# 7_LCD.net
KiCad netlist of a schematic drawn in Altium Designer
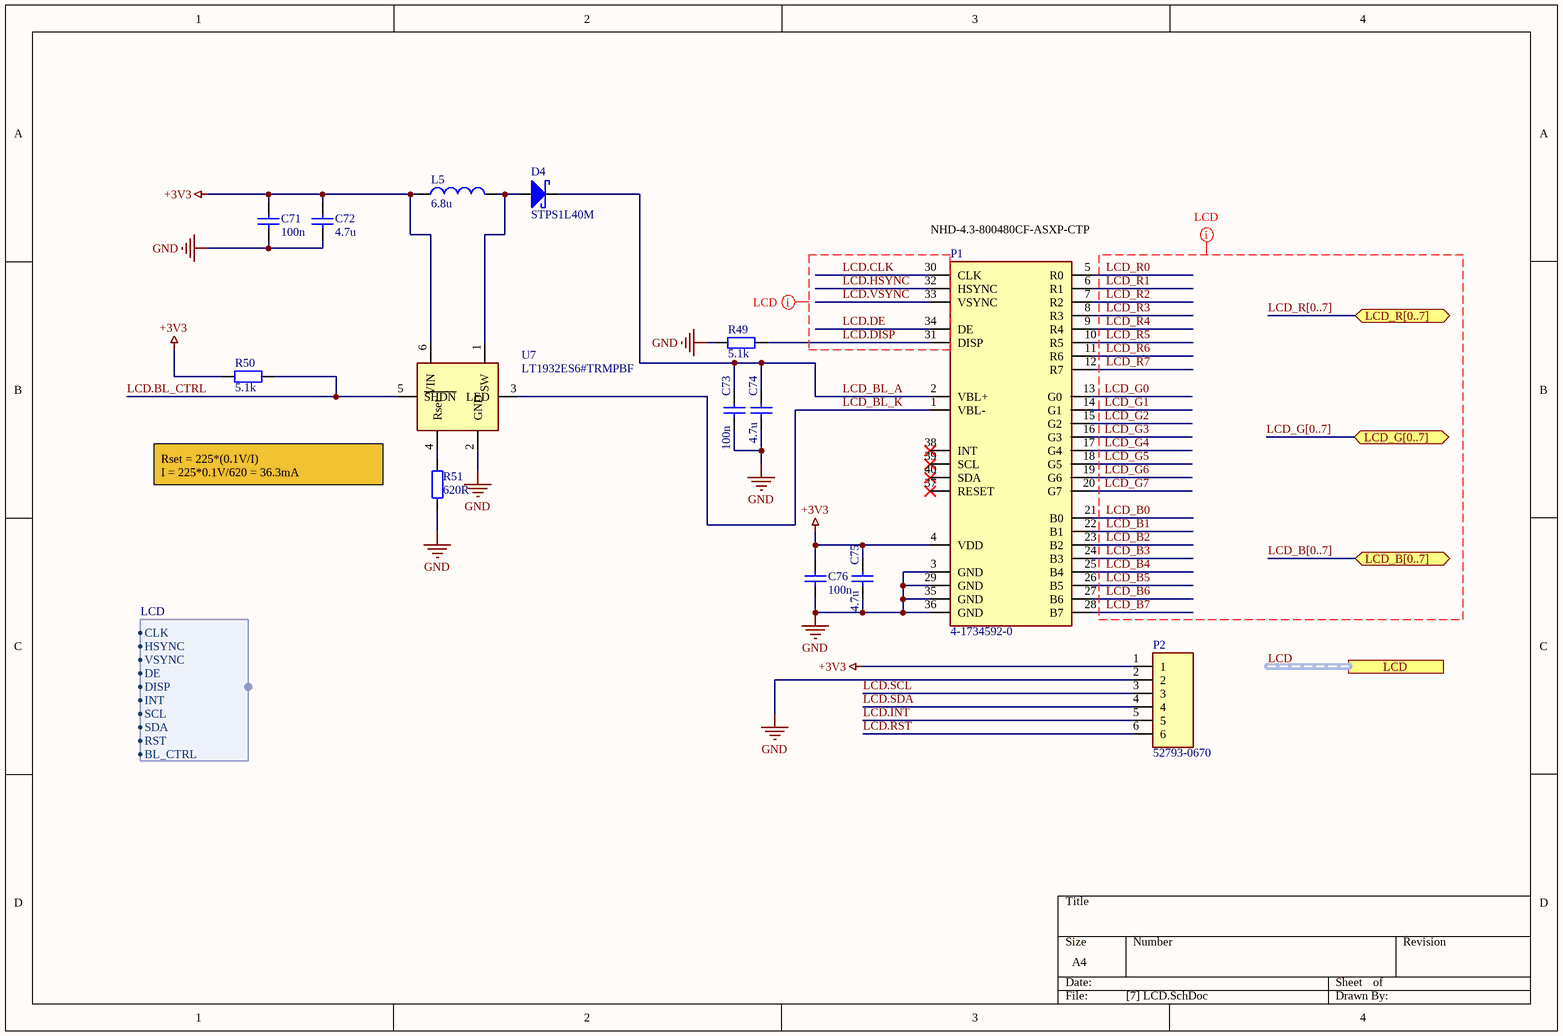
[diagram p0: [7] LCD.SchDoc]

(export (version "E")
  (design (tool "Eeschema 10.0.6"))
  (components
    (comp (ref "C71")
      (value "100n")
      (footprint "STguitar:Capacitor 0603")
      (description "Multilayer Ceramic Capacitors MLCC - SMD/SMT 0603 16VDC 0.1uF 10% X7R")
      (fields
        (field (name "MANUFACTURER PART NUMBER") "EMK107B7104KA-T")
        (field (name "MANUFACTURER") "Taiyo Yuden")
      )
      (libsource (lib "STguitar") (part "Capacitor 100n 10% 0603 EMK107B7104KA-T"))
    )
    (comp (ref "C72")
      (value "4.7u")
      (footprint "STguitar:Capacitor 0603")
      (description "Multilayer Ceramic Capacitors MLCC - SMD/SMT 0603 16VDC 4.7uF 10% X5R")
      (fields
        (field (name "MANUFACTURER PART NUMBER") "EMK107ABJ475KA-T")
        (field (name "MANUFACTURER") "Taiyo Yuden")
      )
      (libsource (lib "STguitar") (part "Capacitor 4.7u 10% 0603 EMK107ABJ475KA-T"))
    )
    (comp (ref "C73")
      (value "100n")
      (footprint "STguitar:Capacitor 0603")
      (description "Multilayer Ceramic Capacitors MLCC - SMD/SMT 0603 16VDC 0.1uF 10% X7R")
      (fields
        (field (name "MANUFACTURER PART NUMBER") "EMK107B7104KA-T")
        (field (name "MANUFACTURER") "Taiyo Yuden")
      )
      (libsource (lib "STguitar") (part "Capacitor 100n 10% 0603 EMK107B7104KA-T"))
    )
    (comp (ref "C74")
      (value "4.7u")
      (footprint "STguitar:Capacitor 0603")
      (description "Multilayer Ceramic Capacitors MLCC - SMD/SMT 0603 16VDC 4.7uF 10% X5R")
      (fields
        (field (name "MANUFACTURER PART NUMBER") "EMK107ABJ475KA-T")
        (field (name "MANUFACTURER") "Taiyo Yuden")
      )
      (libsource (lib "STguitar") (part "Capacitor 4.7u 10% 0603 EMK107ABJ475KA-T"))
    )
    (comp (ref "C75")
      (value "4.7u")
      (footprint "STguitar:Capacitor 0603")
      (description "Multilayer Ceramic Capacitors MLCC - SMD/SMT 0603 16VDC 4.7uF 10% X5R")
      (fields
        (field (name "MANUFACTURER PART NUMBER") "EMK107ABJ475KA-T")
        (field (name "MANUFACTURER") "Taiyo Yuden")
      )
      (libsource (lib "STguitar") (part "Capacitor 4.7u 10% 0603 EMK107ABJ475KA-T"))
    )
    (comp (ref "C76")
      (value "100n")
      (footprint "STguitar:Capacitor 0603")
      (description "Multilayer Ceramic Capacitors MLCC - SMD/SMT 0603 16VDC 0.1uF 10% X7R")
      (fields
        (field (name "MANUFACTURER PART NUMBER") "EMK107B7104KA-T")
        (field (name "MANUFACTURER") "Taiyo Yuden")
      )
      (libsource (lib "STguitar") (part "Capacitor 100n 10% 0603 EMK107B7104KA-T"))
    )
    (comp (ref "D4")
      (value "STPS1L40M")
      (footprint "STguitar:DO216-AA")
      (description "Schottky Diodes & Rectifiers 1.0 Amp 40 Volt")
      (fields (field (name "MANUFACTURER") "ON Semiconductor / Fairchild"))
      (libsource (lib "STguitar") (part "Diode Schottky Diodes & Rectifiers 1.0 Amp 40 Volt STPS1L40M"))
    )
    (comp (ref "L5")
      (value "6.8u")
      (footprint "STguitar:Inductor ASPI")
      (description "Fixed Inductors FIXED IND 6.8UH 900MA 295 MOHM")
      (fields
        (field (name "MANUFACTURER PART NUMBER") "ASPI-2515-6R8M-T2")
        (field (name "MANUFACTURER") "ABRACON")
      )
      (libsource (lib "STguitar") (part "Inductor FIXED IND 6.8UH 900MA 295 MOHM ASPI-2515-6R8M-T2"))
    )
    (comp (ref "P1")
      (value "4-1734592-0")
      (footprint "STguitar:Mechanical FFC 0.5mm 40pin")
      (description "FFC & FPC Connectors FPC CONN 0.5MM PITCH B/C 40P")
      (fields (field (name "MANUFACTURER") "TE Connectivity"))
      (libsource (lib "STguitar") (part "Mechanical FFC & FPC Connectors FPC CONN 0.5MM PITCH B/C 40P 4-1734592-0"))
    )
    (comp (ref "P2")
      (value "52793-0670")
      (footprint "STguitar:Mechanical FFC 1mm 6 pin")
      (description "FFC & FPC Connectors 1.0 FFC Non ZIF HsgA ssySMT 6CktEmbsTpPkg")
      (fields (field (name "MANUFACTURER") "Molex"))
      (libsource (lib "STguitar") (part "Mechanical FFC & FPC Connectors 1.0 FFC Non ZIF HsgA ssySMT 6CktEmbsTpPkg 52793-0670"))
    )
    (comp (ref "R49")
      (value "5.1k")
      (footprint "STguitar:Resistor 0603")
      (description "Thin Film Resistors - SMD 1/10W 5.1K ohm 1% 50ppm")
      (fields
        (field (name "MANUFACTURER PART NUMBER") "RT0603FRE075K1L")
        (field (name "MANUFACTURER") "Yageo")
      )
      (libsource (lib "STguitar") (part "Resistor 5.1k 1% 0603 RT0603FRE075K1L"))
    )
    (comp (ref "R50")
      (value "5.1k")
      (footprint "STguitar:Resistor 0603")
      (description "Thin Film Resistors - SMD 1/10W 5.1K ohm 1% 50ppm")
      (fields
        (field (name "MANUFACTURER PART NUMBER") "RT0603FRE075K1L")
        (field (name "MANUFACTURER") "Yageo")
      )
      (libsource (lib "STguitar") (part "Resistor 5.1k 1% 0603 RT0603FRE075K1L"))
    )
    (comp (ref "R51")
      (value "620R")
      (footprint "STguitar:Resistor 0603")
      (description "Thin Film Resistors - SMD 620 OHM 1% 50PPM 1/10W")
      (fields
        (field (name "MANUFACTURER PART NUMBER") "RT0603FRE07620RL")
        (field (name "MANUFACTURER") "Yageo")
      )
      (libsource (lib "STguitar") (part "Resistor 620R 1% 0603 RT0603FRE07620RL"))
    )
    (comp (ref "U7")
      (value "LT1932ES6#TRMPBF")
      (footprint "STguitar:SOT23-6")
      (description "LED Lighting Drivers Boost Regulator LED Driver")
      (fields (field (name "MANUFACTURER") "Analog Devices"))
      (libsource (lib "STguitar") (part "IC LED Lighting Drivers Boost Regulator LED Driver"))
    )
  )
  (nets
    (net (code "2") (name "+3V3") (class "Default")
      (node (ref "C71") (pin "2") (pinfunction "2_2") (pintype "passive"))
      (node (ref "C72") (pin "2") (pinfunction "2_2") (pintype "passive"))
      (node (ref "C75") (pin "2") (pinfunction "2_2") (pintype "passive"))
      (node (ref "C76") (pin "2") (pinfunction "2_2") (pintype "passive"))
      (node (ref "L5") (pin "1") (pinfunction "1_1") (pintype "passive"))
      (node (ref "P1") (pin "4") (pinfunction "VDD_4") (pintype "passive"))
      (node (ref "P2") (pin "1") (pinfunction "1_1") (pintype "passive"))
      (node (ref "R50") (pin "1") (pinfunction "1_1") (pintype "passive"))
      (node (ref "U7") (pin "6") (pinfunction "VIN_6") (pintype "passive"))
    )
    (net (code "3") (name "/LCD.BL_CTRL") (class "Default")
      (node (ref "R50") (pin "2") (pinfunction "2_2") (pintype "passive"))
      (node (ref "U7") (pin "5") (pinfunction "~{SHDN}_5") (pintype "passive"))
    )
    (net (code "4") (name "/LCD.CLK") (class "Default")
      (node (ref "P1") (pin "30") (pinfunction "CLK_30") (pintype "passive"))
    )
    (net (code "5") (name "/LCD.DE") (class "Default")
      (node (ref "P1") (pin "34") (pinfunction "DE_34") (pintype "passive"))
    )
    (net (code "6") (name "/LCD.DISP") (class "Default")
      (node (ref "P1") (pin "31") (pinfunction "DISP_31") (pintype "passive"))
      (node (ref "R49") (pin "2") (pinfunction "2_2") (pintype "passive"))
    )
    (net (code "7") (name "/LCD.HSYNC") (class "Default")
      (node (ref "P1") (pin "32") (pinfunction "HSYNC_32") (pintype "passive"))
    )
    (net (code "8") (name "/LCD.INT") (class "Default")
      (node (ref "P2") (pin "5") (pinfunction "5_5") (pintype "passive"))
    )
    (net (code "9") (name "/LCD.RST") (class "Default")
      (node (ref "P2") (pin "6") (pinfunction "6_6") (pintype "passive"))
    )
    (net (code "10") (name "/LCD.SCL") (class "Default")
      (node (ref "P2") (pin "3") (pinfunction "3_3") (pintype "passive"))
    )
    (net (code "11") (name "/LCD.SDA") (class "Default")
      (node (ref "P2") (pin "4") (pinfunction "4_4") (pintype "passive"))
    )
    (net (code "12") (name "/LCD.VSYNC") (class "Default")
      (node (ref "P1") (pin "33") (pinfunction "VSYNC_33") (pintype "passive"))
    )
    (net (code "13") (name "/LCD_B0") (class "Default")
      (node (ref "P1") (pin "21") (pinfunction "B0_21") (pintype "passive"))
    )
    (net (code "14") (name "/LCD_B1") (class "Default")
      (node (ref "P1") (pin "22") (pinfunction "B1_22") (pintype "passive"))
    )
    (net (code "15") (name "/LCD_B2") (class "Default")
      (node (ref "P1") (pin "23") (pinfunction "B2_23") (pintype "passive"))
    )
    (net (code "16") (name "/LCD_B3") (class "Default")
      (node (ref "P1") (pin "24") (pinfunction "B3_24") (pintype "passive"))
    )
    (net (code "17") (name "/LCD_B4") (class "Default")
      (node (ref "P1") (pin "25") (pinfunction "B4_25") (pintype "passive"))
    )
    (net (code "18") (name "/LCD_B5") (class "Default")
      (node (ref "P1") (pin "26") (pinfunction "B5_26") (pintype "passive"))
    )
    (net (code "19") (name "/LCD_B6") (class "Default")
      (node (ref "P1") (pin "27") (pinfunction "B6_27") (pintype "passive"))
    )
    (net (code "20") (name "/LCD_B7") (class "Default")
      (node (ref "P1") (pin "28") (pinfunction "B7_28") (pintype "passive"))
    )
    (net (code "21") (name "/LCD_BL_A") (class "Default")
      (node (ref "C73") (pin "2") (pinfunction "2_2") (pintype "passive"))
      (node (ref "C74") (pin "2") (pinfunction "2_2") (pintype "passive"))
      (node (ref "D4") (pin "2") (pinfunction "2_2") (pintype "passive"))
      (node (ref "P1") (pin "2") (pinfunction "VBL+_2") (pintype "passive"))
    )
    (net (code "22") (name "/LCD_BL_K") (class "Default")
      (node (ref "P1") (pin "1") (pinfunction "VBL-_1") (pintype "passive"))
      (node (ref "U7") (pin "3") (pinfunction "LED_3") (pintype "passive"))
    )
    (net (code "24") (name "/LCD_G0") (class "Default")
      (node (ref "P1") (pin "13") (pinfunction "G0_13") (pintype "passive"))
    )
    (net (code "25") (name "/LCD_G1") (class "Default")
      (node (ref "P1") (pin "14") (pinfunction "G1_14") (pintype "passive"))
    )
    (net (code "26") (name "/LCD_G2") (class "Default")
      (node (ref "P1") (pin "15") (pinfunction "G2_15") (pintype "passive"))
    )
    (net (code "27") (name "/LCD_G3") (class "Default")
      (node (ref "P1") (pin "16") (pinfunction "G3_16") (pintype "passive"))
    )
    (net (code "28") (name "/LCD_G4") (class "Default")
      (node (ref "P1") (pin "17") (pinfunction "G4_17") (pintype "passive"))
    )
    (net (code "29") (name "/LCD_G5") (class "Default")
      (node (ref "P1") (pin "18") (pinfunction "G5_18") (pintype "passive"))
    )
    (net (code "30") (name "/LCD_G6") (class "Default")
      (node (ref "P1") (pin "19") (pinfunction "G6_19") (pintype "passive"))
    )
    (net (code "31") (name "/LCD_G7") (class "Default")
      (node (ref "P1") (pin "20") (pinfunction "G7_20") (pintype "passive"))
    )
    (net (code "33") (name "/LCD_R0") (class "Default")
      (node (ref "P1") (pin "5") (pinfunction "R0_5") (pintype "passive"))
    )
    (net (code "34") (name "/LCD_R1") (class "Default")
      (node (ref "P1") (pin "6") (pinfunction "R1_6") (pintype "passive"))
    )
    (net (code "35") (name "/LCD_R2") (class "Default")
      (node (ref "P1") (pin "7") (pinfunction "R2_7") (pintype "passive"))
    )
    (net (code "36") (name "/LCD_R3") (class "Default")
      (node (ref "P1") (pin "8") (pinfunction "R3_8") (pintype "passive"))
    )
    (net (code "37") (name "/LCD_R4") (class "Default")
      (node (ref "P1") (pin "9") (pinfunction "R4_9") (pintype "passive"))
    )
    (net (code "38") (name "/LCD_R5") (class "Default")
      (node (ref "P1") (pin "10") (pinfunction "R5_10") (pintype "passive"))
    )
    (net (code "39") (name "/LCD_R6") (class "Default")
      (node (ref "P1") (pin "11") (pinfunction "R6_11") (pintype "passive"))
    )
    (net (code "40") (name "/LCD_R7") (class "Default")
      (node (ref "P1") (pin "12") (pinfunction "R7_12") (pintype "passive"))
    )
    (net (code "43") (name "GND") (class "Default")
      (node (ref "C71") (pin "1") (pinfunction "1_1") (pintype "passive"))
      (node (ref "C72") (pin "1") (pinfunction "1_1") (pintype "passive"))
      (node (ref "C73") (pin "1") (pinfunction "1_1") (pintype "passive"))
      (node (ref "C74") (pin "1") (pinfunction "1_1") (pintype "passive"))
      (node (ref "C75") (pin "1") (pinfunction "1_1") (pintype "passive"))
      (node (ref "C76") (pin "1") (pinfunction "1_1") (pintype "passive"))
      (node (ref "P1") (pin "29") (pinfunction "GND_29") (pintype "passive"))
      (node (ref "P1") (pin "3") (pinfunction "GND_3") (pintype "passive"))
      (node (ref "P1") (pin "35") (pinfunction "GND_35") (pintype "passive"))
      (node (ref "P1") (pin "36") (pinfunction "GND_36") (pintype "passive"))
      (node (ref "P2") (pin "2") (pinfunction "2_2") (pintype "passive"))
      (node (ref "R49") (pin "1") (pinfunction "1_1") (pintype "passive"))
      (node (ref "R51") (pin "1") (pinfunction "1_1") (pintype "passive"))
      (node (ref "U7") (pin "2") (pinfunction "GND_2") (pintype "passive"))
    )
    (net (code "44") (name "Net-(U7-Rset)") (class "Default")
      (node (ref "R51") (pin "2") (pinfunction "2_2") (pintype "passive"))
      (node (ref "U7") (pin "4") (pinfunction "Rset_4") (pintype "passive"))
    )
    (net (code "45") (name "Net-(U7-SW)") (class "Default")
      (node (ref "D4") (pin "1") (pinfunction "1_1") (pintype "passive"))
      (node (ref "L5") (pin "2") (pinfunction "2_2") (pintype "passive"))
      (node (ref "U7") (pin "1") (pinfunction "SW_1") (pintype "passive"))
    )
    (net (code "46") (name "unconnected-(P1-INT-Pad38)") (class "Default")
      (node (ref "P1") (pin "38") (pinfunction "INT_38") (pintype "passive+no_connect"))
    )
    (net (code "47") (name "unconnected-(P1-RESET-Pad37)") (class "Default")
      (node (ref "P1") (pin "37") (pinfunction "RESET_37") (pintype "passive+no_connect"))
    )
    (net (code "48") (name "unconnected-(P1-SCL-Pad39)") (class "Default")
      (node (ref "P1") (pin "39") (pinfunction "SCL_39") (pintype "passive+no_connect"))
    )
    (net (code "49") (name "unconnected-(P1-SDA-Pad40)") (class "Default")
      (node (ref "P1") (pin "40") (pinfunction "SDA_40") (pintype "passive+no_connect"))
    )
  )
)
